# I2C_decagon2_0.net
KiCad netlist of a schematic drawn in EAGLE
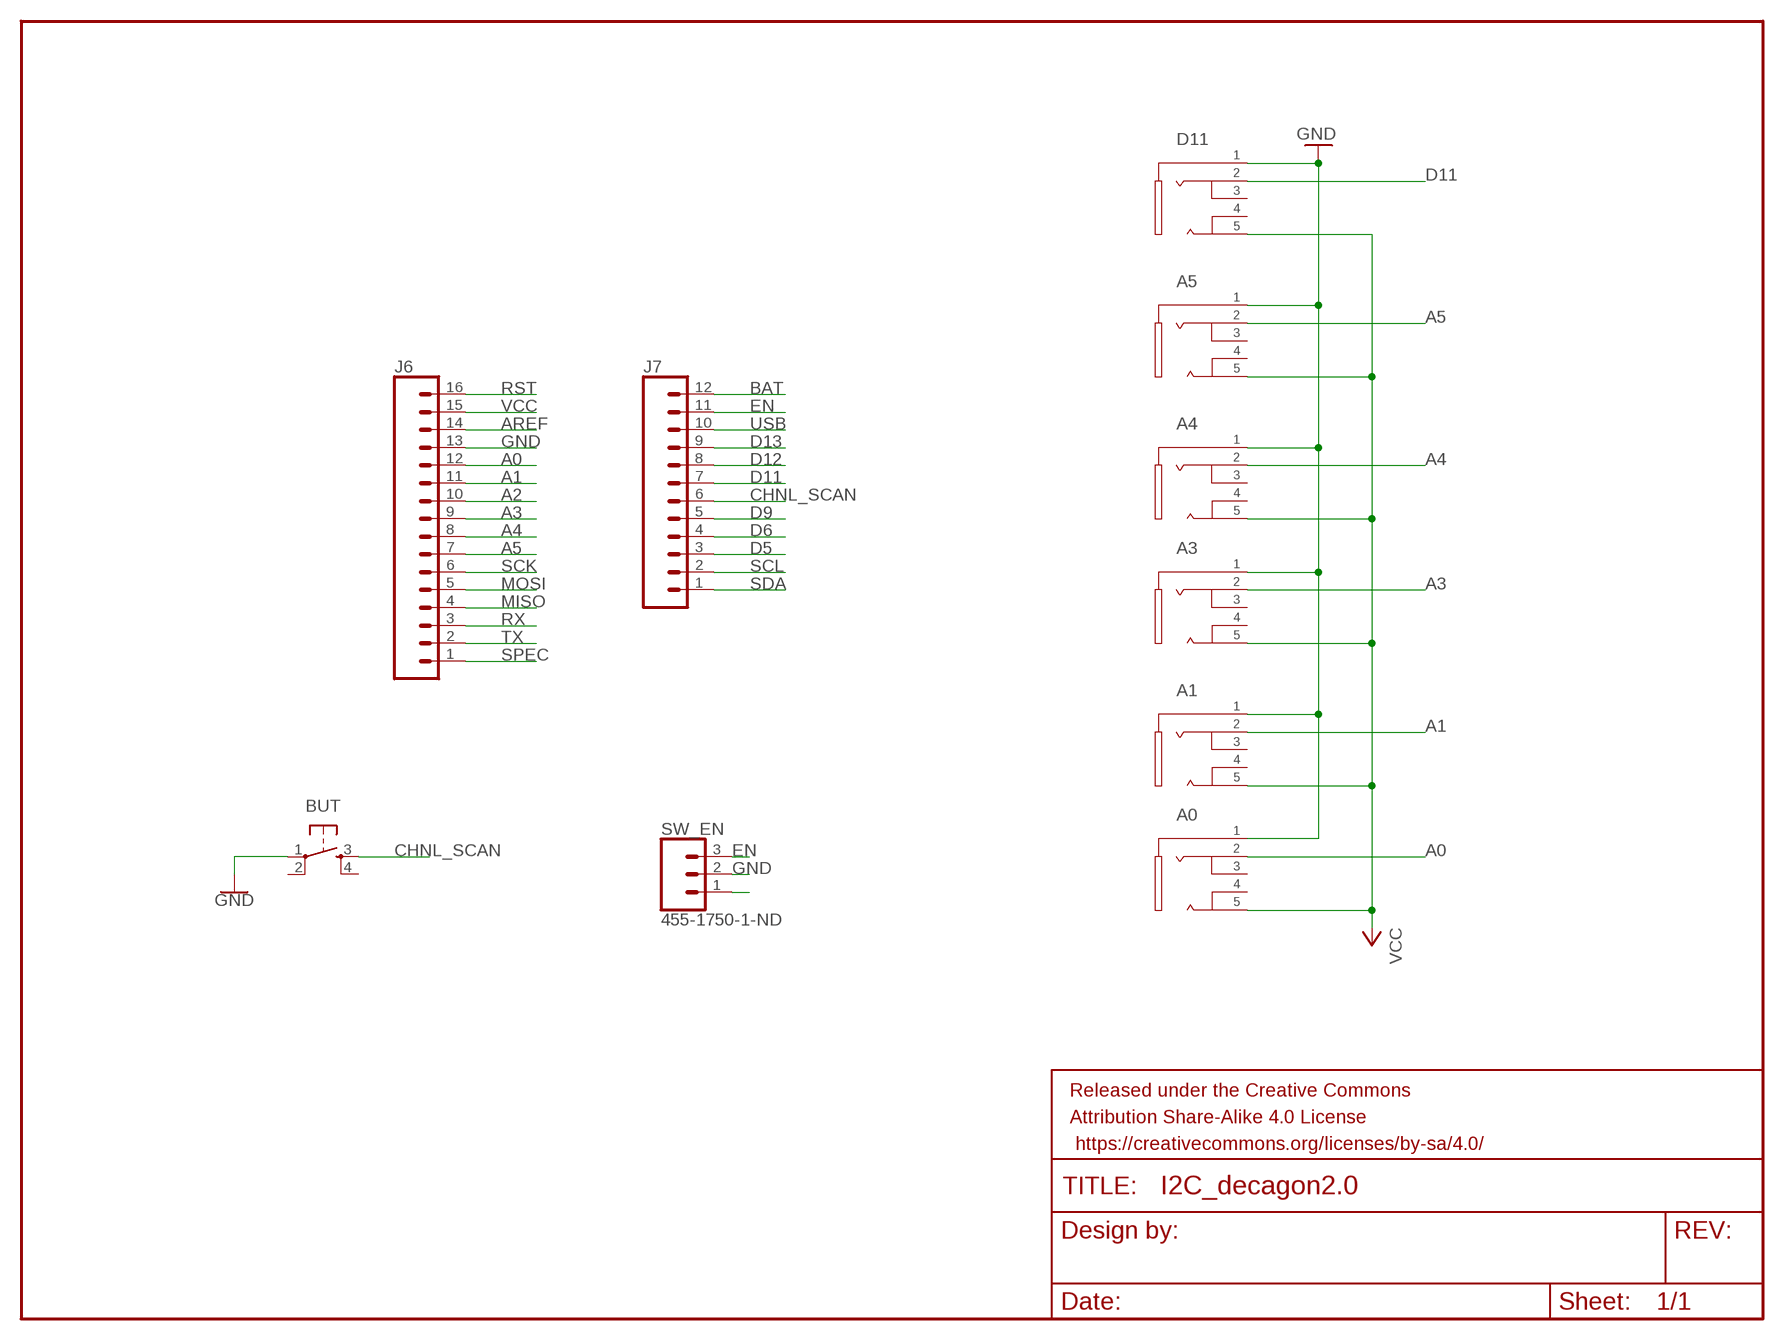
[diagram p0: schematic, sheet 1]

(export (version "E")
  (design (tool "Eeschema 10.0.6"))
  (components
    (comp (ref "A0")
      (value "JW-PJ-307-5H")
      (footprint "eagle-import:JW-PJ-307-5H")
      (libsource (lib "eagle-import") (part "JW-PJ-307-5H"))
    )
    (comp (ref "A1")
      (value "JW-PJ-307-5H")
      (footprint "eagle-import:JW-PJ-307-5H")
      (libsource (lib "eagle-import") (part "JW-PJ-307-5H"))
    )
    (comp (ref "A3")
      (value "JW-PJ-307-5H")
      (footprint "eagle-import:JW-PJ-307-5H")
      (libsource (lib "eagle-import") (part "JW-PJ-307-5H"))
    )
    (comp (ref "A4")
      (value "JW-PJ-307-5H")
      (footprint "eagle-import:JW-PJ-307-5H")
      (libsource (lib "eagle-import") (part "JW-PJ-307-5H"))
    )
    (comp (ref "A5")
      (value "JW-PJ-307-5H")
      (footprint "eagle-import:JW-PJ-307-5H")
      (libsource (lib "eagle-import") (part "JW-PJ-307-5H"))
    )
    (comp (ref "BUT")
      (value "TAC_SWITCHPTH")
      (footprint "eagle-import:TACTILE-PTH")
      (libsource (lib "eagle-import") (part "TAC_SWITCHPTH"))
    )
    (comp (ref "D11")
      (value "JW-PJ-307-5H")
      (footprint "eagle-import:JW-PJ-307-5H")
      (libsource (lib "eagle-import") (part "JW-PJ-307-5H"))
    )
    (comp (ref "FRAME1")
      (value "FRAME-LETTER")
      (footprint "eagle-import:CREATIVE_COMMONS")
      (libsource (lib "eagle-import") (part "FRAME-LETTER"))
    )
    (comp (ref "J6")
      (value "CONN_16")
      (footprint "eagle-import:1X16")
      (libsource (lib "eagle-import") (part "CONN_16"))
    )
    (comp (ref "J7")
      (value "CONN_12")
      (footprint "eagle-import:1X12")
      (libsource (lib "eagle-import") (part "CONN_12"))
    )
    (comp (ref "SW_EN")
      (value "455-1750-1-ND")
      (footprint "eagle-import:1X03")
      (libsource (lib "eagle-import") (part "CONN_03"))
    )
  )
  (nets
    (net (code "1") (name "/A0") (class "Default")
      (node (ref "A0") (pin "2") (pinfunction "2_2") (pintype "passive"))
      (node (ref "J6") (pin "12") (pinfunction "12_12") (pintype "passive"))
    )
    (net (code "2") (name "/A1") (class "Default")
      (node (ref "A1") (pin "2") (pinfunction "2_2") (pintype "passive"))
      (node (ref "J6") (pin "11") (pinfunction "11_11") (pintype "passive"))
    )
    (net (code "3") (name "/A2") (class "Default")
      (node (ref "J6") (pin "10") (pinfunction "10_10") (pintype "passive"))
    )
    (net (code "4") (name "/A3") (class "Default")
      (node (ref "A3") (pin "2") (pinfunction "2_2") (pintype "passive"))
      (node (ref "J6") (pin "9") (pinfunction "9_9") (pintype "passive"))
    )
    (net (code "5") (name "/A4") (class "Default")
      (node (ref "A4") (pin "2") (pinfunction "2_2") (pintype "passive"))
      (node (ref "J6") (pin "8") (pinfunction "8_8") (pintype "passive"))
    )
    (net (code "6") (name "/A5") (class "Default")
      (node (ref "A5") (pin "2") (pinfunction "2_2") (pintype "passive"))
      (node (ref "J6") (pin "7") (pinfunction "7_7") (pintype "passive"))
    )
    (net (code "7") (name "/AREF") (class "Default")
      (node (ref "J6") (pin "14") (pinfunction "14_14") (pintype "passive"))
    )
    (net (code "8") (name "/BAT") (class "Default")
      (node (ref "J7") (pin "12") (pinfunction "12_12") (pintype "passive"))
    )
    (net (code "9") (name "/CHNL_SCAN") (class "Default")
      (node (ref "BUT") (pin "3") (pinfunction "3_3") (pintype "passive"))
      (node (ref "J7") (pin "6") (pinfunction "6_6") (pintype "passive"))
    )
    (net (code "10") (name "/D5") (class "Default")
      (node (ref "J7") (pin "3") (pinfunction "3_3") (pintype "passive"))
    )
    (net (code "11") (name "/D6") (class "Default")
      (node (ref "J7") (pin "4") (pinfunction "4_4") (pintype "passive"))
    )
    (net (code "12") (name "/D9") (class "Default")
      (node (ref "J7") (pin "5") (pinfunction "5_5") (pintype "passive"))
    )
    (net (code "13") (name "/D11") (class "Default")
      (node (ref "D11") (pin "2") (pinfunction "2_2") (pintype "passive"))
      (node (ref "J7") (pin "7") (pinfunction "7_7") (pintype "passive"))
    )
    (net (code "14") (name "/D12") (class "Default")
      (node (ref "J7") (pin "8") (pinfunction "8_8") (pintype "passive"))
    )
    (net (code "15") (name "/D13") (class "Default")
      (node (ref "J7") (pin "9") (pinfunction "9_9") (pintype "passive"))
    )
    (net (code "16") (name "/EN") (class "Default")
      (node (ref "J7") (pin "11") (pinfunction "11_11") (pintype "passive"))
      (node (ref "SW_EN") (pin "3") (pinfunction "3_3") (pintype "passive"))
    )
    (net (code "17") (name "/MISO") (class "Default")
      (node (ref "J6") (pin "4") (pinfunction "4_4") (pintype "passive"))
    )
    (net (code "18") (name "/MOSI") (class "Default")
      (node (ref "J6") (pin "5") (pinfunction "5_5") (pintype "passive"))
    )
    (net (code "19") (name "/RST") (class "Default")
      (node (ref "J6") (pin "16") (pinfunction "16_16") (pintype "passive"))
    )
    (net (code "20") (name "/RX") (class "Default")
      (node (ref "J6") (pin "3") (pinfunction "3_3") (pintype "passive"))
    )
    (net (code "21") (name "/SCK") (class "Default")
      (node (ref "J6") (pin "6") (pinfunction "6_6") (pintype "passive"))
    )
    (net (code "22") (name "/SCL") (class "Default")
      (node (ref "J7") (pin "2") (pinfunction "2_2") (pintype "passive"))
    )
    (net (code "23") (name "/SDA") (class "Default")
      (node (ref "J7") (pin "1") (pinfunction "1_1") (pintype "passive"))
    )
    (net (code "24") (name "/SPEC") (class "Default")
      (node (ref "J6") (pin "1") (pinfunction "1_1") (pintype "passive"))
    )
    (net (code "25") (name "/TX") (class "Default")
      (node (ref "J6") (pin "2") (pinfunction "2_2") (pintype "passive"))
    )
    (net (code "26") (name "/USB") (class "Default")
      (node (ref "J7") (pin "10") (pinfunction "10_10") (pintype "passive"))
    )
    (net (code "27") (name "GND") (class "Default")
      (node (ref "A0") (pin "1") (pinfunction "1_1") (pintype "passive"))
      (node (ref "A1") (pin "1") (pinfunction "1_1") (pintype "passive"))
      (node (ref "A3") (pin "1") (pinfunction "1_1") (pintype "passive"))
      (node (ref "A4") (pin "1") (pinfunction "1_1") (pintype "passive"))
      (node (ref "A5") (pin "1") (pinfunction "1_1") (pintype "passive"))
      (node (ref "BUT") (pin "1") (pinfunction "1_1") (pintype "passive"))
      (node (ref "D11") (pin "1") (pinfunction "1_1") (pintype "passive"))
      (node (ref "J6") (pin "13") (pinfunction "13_13") (pintype "passive"))
      (node (ref "SW_EN") (pin "2") (pinfunction "2_2") (pintype "passive"))
    )
    (net (code "28") (name "VCC") (class "Default")
      (node (ref "A0") (pin "5") (pinfunction "5_5") (pintype "passive"))
      (node (ref "A1") (pin "5") (pinfunction "5_5") (pintype "passive"))
      (node (ref "A3") (pin "5") (pinfunction "5_5") (pintype "passive"))
      (node (ref "A4") (pin "5") (pinfunction "5_5") (pintype "passive"))
      (node (ref "A5") (pin "5") (pinfunction "5_5") (pintype "passive"))
      (node (ref "D11") (pin "5") (pinfunction "5_5") (pintype "passive"))
      (node (ref "J6") (pin "15") (pinfunction "15_15") (pintype "passive"))
    )
    (net (code "29") (name "unconnected-(A0-Pad3)") (class "Default")
      (node (ref "A0") (pin "3") (pinfunction "3_3") (pintype "passive"))
    )
    (net (code "30") (name "unconnected-(A0-Pad4)") (class "Default")
      (node (ref "A0") (pin "4") (pinfunction "4_4") (pintype "passive"))
    )
    (net (code "31") (name "unconnected-(A1-Pad3)") (class "Default")
      (node (ref "A1") (pin "3") (pinfunction "3_3") (pintype "passive"))
    )
    (net (code "32") (name "unconnected-(A1-Pad4)") (class "Default")
      (node (ref "A1") (pin "4") (pinfunction "4_4") (pintype "passive"))
    )
    (net (code "33") (name "unconnected-(A3-Pad3)") (class "Default")
      (node (ref "A3") (pin "3") (pinfunction "3_3") (pintype "passive"))
    )
    (net (code "34") (name "unconnected-(A3-Pad4)") (class "Default")
      (node (ref "A3") (pin "4") (pinfunction "4_4") (pintype "passive"))
    )
    (net (code "35") (name "unconnected-(A4-Pad3)") (class "Default")
      (node (ref "A4") (pin "3") (pinfunction "3_3") (pintype "passive"))
    )
    (net (code "36") (name "unconnected-(A4-Pad4)") (class "Default")
      (node (ref "A4") (pin "4") (pinfunction "4_4") (pintype "passive"))
    )
    (net (code "37") (name "unconnected-(A5-Pad3)") (class "Default")
      (node (ref "A5") (pin "3") (pinfunction "3_3") (pintype "passive"))
    )
    (net (code "38") (name "unconnected-(A5-Pad4)") (class "Default")
      (node (ref "A5") (pin "4") (pinfunction "4_4") (pintype "passive"))
    )
    (net (code "39") (name "unconnected-(BUT-Pad2)") (class "Default")
      (node (ref "BUT") (pin "2") (pinfunction "2_2") (pintype "passive"))
    )
    (net (code "40") (name "unconnected-(BUT-Pad4)") (class "Default")
      (node (ref "BUT") (pin "4") (pinfunction "4_4") (pintype "passive"))
    )
    (net (code "41") (name "unconnected-(D11-Pad3)") (class "Default")
      (node (ref "D11") (pin "3") (pinfunction "3_3") (pintype "passive"))
    )
    (net (code "42") (name "unconnected-(D11-Pad4)") (class "Default")
      (node (ref "D11") (pin "4") (pinfunction "4_4") (pintype "passive"))
    )
    (net (code "43") (name "unconnected-(SW_EN-Pad1)") (class "Default")
      (node (ref "SW_EN") (pin "1") (pinfunction "1_1") (pintype "passive"))
    )
  )
)
